# Main.net
KiCad netlist of a schematic drawn in Altium Designer
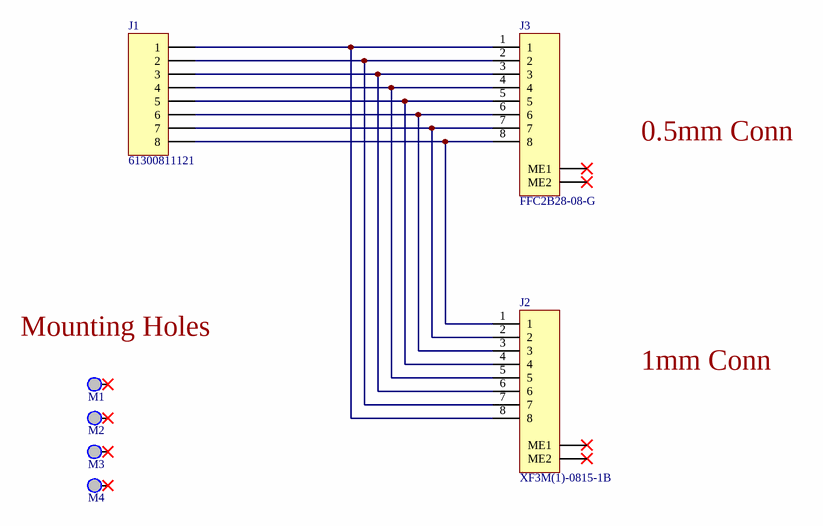
[diagram p0: Main.SchDoc]

(export (version "E")
  (design (tool "Eeschema 10.0.6"))
  (components
    (comp (ref "J1")
      (value "61300811121")
      (footprint "HDR-V-1X8")
      (description "THT Vertical Pin Header WR-PHD, Pitch 2.54 mm, Single Row, 8 pins")
      (libsource (lib "intercreate") (part "HDR-V-1X8-M"))
    )
    (comp (ref "J2")
      (value "XF3M(1)-0815-1B")
      (footprint "CONN-FFC-H-8P-1MM")
      (description "1.0-mm Pitch, Dual Contact ; For FPC/FFC, 8 Contacts, RoHS")
      (libsource (lib "intercreate") (part "CONN-FFC-H-8P-1MM"))
    )
    (comp (ref "J3")
      (value "FFC2B28-08-G")
      (footprint "CONN-FFC-H-8P-0.5MM")
      (description "FFC & FPC Connectors 08W, 0.5mm FFC Con, R/A, Dual Cont, B/Flp, H1.0mm, Gld, SMT, T&R")
      (libsource (lib "intercreate") (part "CONN-FFC-H-8P-0.5MM"))
    )
    (comp (ref "M1")
      (value "MTG_HOLE")
      (footprint "MH_P_2.5MM")
      (description "MTG HOLE PLATED VARIOUS SIZES")
      (libsource (lib "intercreate") (part "MTG_HOLE"))
    )
    (comp (ref "M2")
      (value "MTG_HOLE")
      (footprint "MH_P_2.5MM")
      (description "MTG HOLE PLATED VARIOUS SIZES")
      (libsource (lib "intercreate") (part "MTG_HOLE"))
    )
    (comp (ref "M3")
      (value "MTG_HOLE")
      (footprint "MH_P_2.5MM")
      (description "MTG HOLE PLATED VARIOUS SIZES")
      (libsource (lib "intercreate") (part "MTG_HOLE"))
    )
    (comp (ref "M4")
      (value "MTG_HOLE")
      (footprint "MH_P_2.5MM")
      (description "MTG HOLE PLATED VARIOUS SIZES")
      (libsource (lib "intercreate") (part "MTG_HOLE"))
    )
  )
  (nets
    (net (code "1") (name "Net-(J1-Pad1)") (class "Default")
      (node (ref "J1") (pin "1") (pinfunction "1_1") (pintype "passive"))
      (node (ref "J2") (pin "8") (pinfunction "8_8") (pintype "passive"))
      (node (ref "J3") (pin "1") (pinfunction "1_1") (pintype "passive"))
    )
    (net (code "2") (name "Net-(J1-Pad2)") (class "Default")
      (node (ref "J1") (pin "2") (pinfunction "2_2") (pintype "passive"))
      (node (ref "J2") (pin "7") (pinfunction "7_7") (pintype "passive"))
      (node (ref "J3") (pin "2") (pinfunction "2_2") (pintype "passive"))
    )
    (net (code "3") (name "Net-(J1-Pad3)") (class "Default")
      (node (ref "J1") (pin "3") (pinfunction "3_3") (pintype "passive"))
      (node (ref "J2") (pin "6") (pinfunction "6_6") (pintype "passive"))
      (node (ref "J3") (pin "3") (pinfunction "3_3") (pintype "passive"))
    )
    (net (code "4") (name "Net-(J1-Pad4)") (class "Default")
      (node (ref "J1") (pin "4") (pinfunction "4_4") (pintype "passive"))
      (node (ref "J2") (pin "5") (pinfunction "5_5") (pintype "passive"))
      (node (ref "J3") (pin "4") (pinfunction "4_4") (pintype "passive"))
    )
    (net (code "5") (name "Net-(J1-Pad5)") (class "Default")
      (node (ref "J1") (pin "5") (pinfunction "5_5") (pintype "passive"))
      (node (ref "J2") (pin "4") (pinfunction "4_4") (pintype "passive"))
      (node (ref "J3") (pin "5") (pinfunction "5_5") (pintype "passive"))
    )
    (net (code "6") (name "Net-(J1-Pad6)") (class "Default")
      (node (ref "J1") (pin "6") (pinfunction "6_6") (pintype "passive"))
      (node (ref "J2") (pin "3") (pinfunction "3_3") (pintype "passive"))
      (node (ref "J3") (pin "6") (pinfunction "6_6") (pintype "passive"))
    )
    (net (code "7") (name "Net-(J1-Pad7)") (class "Default")
      (node (ref "J1") (pin "7") (pinfunction "7_7") (pintype "passive"))
      (node (ref "J2") (pin "2") (pinfunction "2_2") (pintype "passive"))
      (node (ref "J3") (pin "7") (pinfunction "7_7") (pintype "passive"))
    )
    (net (code "8") (name "Net-(J1-Pad8)") (class "Default")
      (node (ref "J1") (pin "8") (pinfunction "8_8") (pintype "passive"))
      (node (ref "J2") (pin "1") (pinfunction "1_1") (pintype "passive"))
      (node (ref "J3") (pin "8") (pinfunction "8_8") (pintype "passive"))
    )
    (net (code "9") (name "unconnected-(J2-PadME1)") (class "Default")
      (node (ref "J2") (pin "ME1") (pinfunction "ME1_ME1") (pintype "passive+no_connect"))
    )
    (net (code "10") (name "unconnected-(J2-PadME2)") (class "Default")
      (node (ref "J2") (pin "ME2") (pinfunction "ME2_ME2") (pintype "passive+no_connect"))
    )
    (net (code "11") (name "unconnected-(J3-PadME1)") (class "Default")
      (node (ref "J3") (pin "ME1") (pinfunction "ME1_ME1") (pintype "passive+no_connect"))
    )
    (net (code "12") (name "unconnected-(J3-PadME2)") (class "Default")
      (node (ref "J3") (pin "ME2") (pinfunction "ME2_ME2") (pintype "passive+no_connect"))
    )
    (net (code "13") (name "unconnected-(M1-Pad1)") (class "Default")
      (node (ref "M1") (pin "1") (pinfunction "1_1") (pintype "passive+no_connect"))
    )
    (net (code "14") (name "unconnected-(M2-Pad1)") (class "Default")
      (node (ref "M2") (pin "1") (pinfunction "1_1") (pintype "passive+no_connect"))
    )
    (net (code "15") (name "unconnected-(M3-Pad1)") (class "Default")
      (node (ref "M3") (pin "1") (pinfunction "1_1") (pintype "passive+no_connect"))
    )
    (net (code "16") (name "unconnected-(M4-Pad1)") (class "Default")
      (node (ref "M4") (pin "1") (pinfunction "1_1") (pintype "passive+no_connect"))
    )
  )
)
